# SCH_08_ADC.net
KiCad netlist of a schematic drawn in Altium Designer
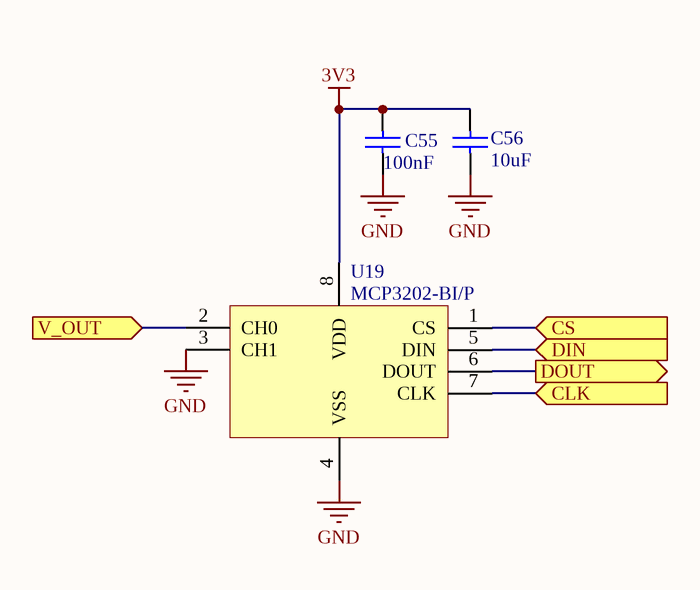
[diagram p0: SCH_08_ADC.SchDoc]

(export (version "E")
  (design (tool "Eeschema 10.0.6"))
  (components
    (comp (ref "C55")
      (value "100nF")
      (footprint "WCAP-CSGP_0603_L1.6W0.8H0.8_Reflow")
      (description "WCAP-CSGP Multilayer Ceramic Chip Capacitor, General Purpose, size 0603, X7R, 100nF, 50VDC")
      (fields
        (field (name "MANUFACTURER PART NUMBER") "885012206095")
        (field (name "MANUFACTURER") "Wurth Elektronik")
      )
      (libsource (lib "Altium_WCAP-CSGP (rev24b)") (part "885012206095"))
    )
    (comp (ref "C56")
      (value "10uF")
      (footprint "WCAP-CSGP_0603_L1.6W0.8H0.8_Reflow")
      (description "WCAP-CSGP Multilayer Ceramic Chip Capacitor, General Purpose, size 0603, X5R, 10uF, 25VDC")
      (fields
        (field (name "MANUFACTURER PART NUMBER") "885012106031")
        (field (name "MANUFACTURER") "Wurth Elektronik")
      )
      (libsource (lib "Altium_WCAP-CSGP (rev24b)") (part "885012106031"))
    )
    (comp (ref "U19")
      (value "MCP3202-BI/P")
      (footprint "DIP787W46P254L927H533Q8")
      (libsource (lib "MCP3202-BI-P") (part "MCP3202-BI/P"))
    )
  )
  (nets
    (net (code "1") (name "/CLK") (class "Default")
      (node (ref "U19") (pin "7") (pinfunction "CLK_7") (pintype "passive"))
    )
    (net (code "2") (name "/CS") (class "Default")
      (node (ref "U19") (pin "1") (pinfunction "CS_1") (pintype "passive"))
    )
    (net (code "3") (name "/DIN") (class "Default")
      (node (ref "U19") (pin "5") (pinfunction "DIN_5") (pintype "passive"))
    )
    (net (code "4") (name "/DOUT") (class "Default")
      (node (ref "U19") (pin "6") (pinfunction "DOUT_6") (pintype "passive"))
    )
    (net (code "5") (name "/V_OUT") (class "Default")
      (node (ref "U19") (pin "2") (pinfunction "CH0_2") (pintype "passive"))
    )
    (net (code "6") (name "3V3") (class "Default")
      (node (ref "C55") (pin "2") (pinfunction "2_2") (pintype "passive"))
      (node (ref "C56") (pin "2") (pinfunction "2_2") (pintype "passive"))
      (node (ref "U19") (pin "8") (pinfunction "VDD_8") (pintype "passive"))
    )
    (net (code "7") (name "GND") (class "Default")
      (node (ref "C55") (pin "1") (pinfunction "1_1") (pintype "passive"))
      (node (ref "C56") (pin "1") (pinfunction "1_1") (pintype "passive"))
      (node (ref "U19") (pin "3") (pinfunction "CH1_3") (pintype "passive"))
      (node (ref "U19") (pin "4") (pinfunction "VSS_4") (pintype "passive"))
    )
  )
)
